# DSPCONN_4-7.net
KiCad netlist of a schematic drawn in Altium Designer
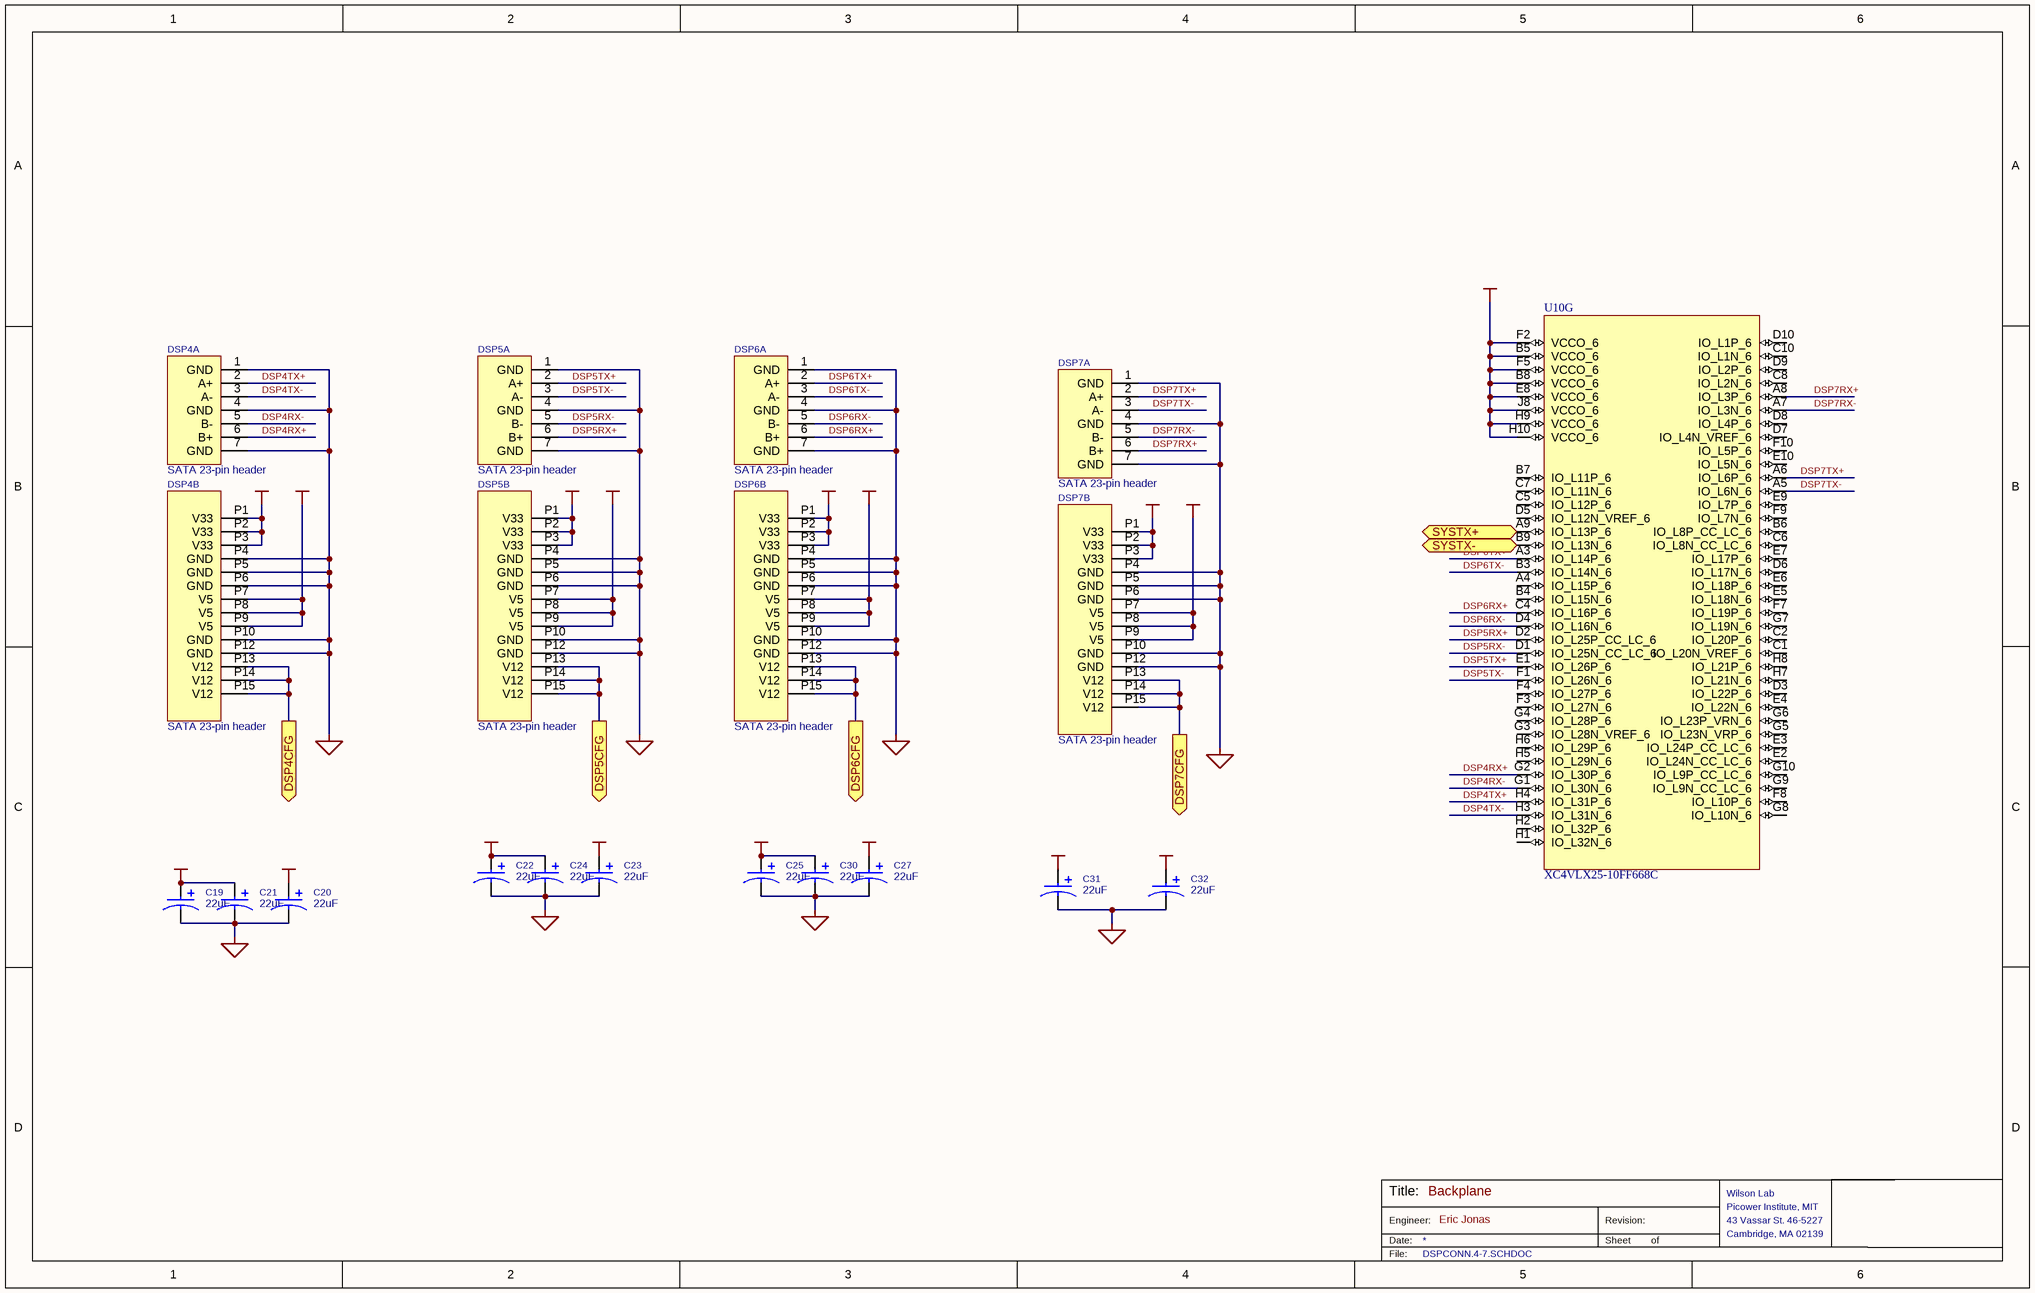
[diagram p0: DSPCONN.4-7.SCHDOC]

(export (version "E")
  (design (tool "Eeschema 10.0.6"))
  (components
    (comp (ref "C19")
      (value "22uF")
      (footprint "6032")
      (description "Standard Capacitor")
      (fields (field (name "Comment") "POLCAP2"))
      (libsource (lib "parts") (part "POLCAP2"))
    )
    (comp (ref "C20")
      (value "22uF")
      (footprint "6032")
      (description "Standard Capacitor")
      (fields (field (name "Comment") "POLCAP2"))
      (libsource (lib "parts") (part "POLCAP2"))
    )
    (comp (ref "C21")
      (value "22uF")
      (footprint "6032")
      (description "Standard Capacitor")
      (fields (field (name "Comment") "POLCAP2"))
      (libsource (lib "parts") (part "POLCAP2"))
    )
    (comp (ref "C22")
      (value "22uF")
      (footprint "6032")
      (description "Standard Capacitor")
      (fields (field (name "Comment") "POLCAP2"))
      (libsource (lib "parts") (part "POLCAP2"))
    )
    (comp (ref "C23")
      (value "22uF")
      (footprint "6032")
      (description "Standard Capacitor")
      (fields (field (name "Comment") "POLCAP2"))
      (libsource (lib "parts") (part "POLCAP2"))
    )
    (comp (ref "C24")
      (value "22uF")
      (footprint "6032")
      (description "Standard Capacitor")
      (fields (field (name "Comment") "POLCAP2"))
      (libsource (lib "parts") (part "POLCAP2"))
    )
    (comp (ref "C25")
      (value "22uF")
      (footprint "6032")
      (description "Standard Capacitor")
      (fields (field (name "Comment") "POLCAP2"))
      (libsource (lib "parts") (part "POLCAP2"))
    )
    (comp (ref "C27")
      (value "22uF")
      (footprint "6032")
      (description "Standard Capacitor")
      (fields (field (name "Comment") "POLCAP2"))
      (libsource (lib "parts") (part "POLCAP2"))
    )
    (comp (ref "C30")
      (value "22uF")
      (footprint "6032")
      (description "Standard Capacitor")
      (fields (field (name "Comment") "POLCAP2"))
      (libsource (lib "parts") (part "POLCAP2"))
    )
    (comp (ref "C31")
      (value "22uF")
      (footprint "6032")
      (description "Standard Capacitor")
      (fields (field (name "Comment") "POLCAP2"))
      (libsource (lib "parts") (part "POLCAP2"))
    )
    (comp (ref "C32")
      (value "22uF")
      (footprint "6032")
      (description "Standard Capacitor")
      (fields (field (name "Comment") "POLCAP2"))
      (libsource (lib "parts") (part "POLCAP2"))
    )
    (comp (ref "DSP4")
      (value "SATA 23-pin header")
      (footprint "MOLEX 87713-1001")
      (libsource (lib "parts") (part "SATA-23"))
    )
    (comp (ref "DSP5")
      (value "SATA 23-pin header")
      (footprint "MOLEX 87713-1001")
      (libsource (lib "parts") (part "SATA-23"))
    )
    (comp (ref "DSP6")
      (value "SATA 23-pin header")
      (footprint "MOLEX 87713-1001")
      (libsource (lib "parts") (part "SATA-23"))
    )
    (comp (ref "DSP7")
      (value "SATA 23-pin header")
      (footprint "MOLEX 87713-1001")
      (libsource (lib "parts") (part "SATA-23"))
    )
    (comp (ref "U10")
      (value "XC4VLX25-10FF668C")
      (footprint "Xilinx FF668")
      (description "Xilinx Virtex-4")
      (libsource (lib "parts") (part "XC4VLX25-10FF668C"))
    )
  )
  (nets
    (net (code "1") (name "+2.5VCC") (class "Default")
      (node (ref "U10") (pin "B5") (pinfunction "VCCO_6_B5") (pintype "bidirectional"))
      (node (ref "U10") (pin "B8") (pinfunction "VCCO_6_B8") (pintype "bidirectional"))
      (node (ref "U10") (pin "E8") (pinfunction "VCCO_6_E8") (pintype "bidirectional"))
      (node (ref "U10") (pin "F2") (pinfunction "VCCO_6_F2") (pintype "bidirectional"))
      (node (ref "U10") (pin "F5") (pinfunction "VCCO_6_F5") (pintype "bidirectional"))
      (node (ref "U10") (pin "H10") (pinfunction "VCCO_6_H10") (pintype "bidirectional"))
      (node (ref "U10") (pin "H9") (pinfunction "VCCO_6_H9") (pintype "bidirectional"))
      (node (ref "U10") (pin "J8") (pinfunction "VCCO_6_J8") (pintype "bidirectional"))
    )
    (net (code "2") (name "+5VCC") (class "Default")
      (node (ref "C20") (pin "1") (pintype "passive"))
      (node (ref "C23") (pin "1") (pintype "passive"))
      (node (ref "C27") (pin "1") (pintype "passive"))
      (node (ref "C32") (pin "1") (pintype "passive"))
      (node (ref "DSP4") (pin "P7") (pinfunction "V5_P7") (pintype "passive"))
      (node (ref "DSP4") (pin "P8") (pinfunction "V5_P8") (pintype "passive"))
      (node (ref "DSP4") (pin "P9") (pinfunction "V5_P9") (pintype "passive"))
      (node (ref "DSP5") (pin "P7") (pinfunction "V5_P7") (pintype "passive"))
      (node (ref "DSP5") (pin "P8") (pinfunction "V5_P8") (pintype "passive"))
      (node (ref "DSP5") (pin "P9") (pinfunction "V5_P9") (pintype "passive"))
      (node (ref "DSP6") (pin "P7") (pinfunction "V5_P7") (pintype "passive"))
      (node (ref "DSP6") (pin "P8") (pinfunction "V5_P8") (pintype "passive"))
      (node (ref "DSP6") (pin "P9") (pinfunction "V5_P9") (pintype "passive"))
      (node (ref "DSP7") (pin "P7") (pinfunction "V5_P7") (pintype "passive"))
      (node (ref "DSP7") (pin "P8") (pinfunction "V5_P8") (pintype "passive"))
      (node (ref "DSP7") (pin "P9") (pinfunction "V5_P9") (pintype "passive"))
    )
    (net (code "3") (name "/DSP4CFG") (class "Default")
      (node (ref "DSP4") (pin "P13") (pinfunction "V12_P13") (pintype "passive"))
      (node (ref "DSP4") (pin "P14") (pinfunction "V12_P14") (pintype "passive"))
      (node (ref "DSP4") (pin "P15") (pinfunction "V12_P15") (pintype "passive"))
    )
    (net (code "4") (name "/DSP4RX+") (class "Default")
      (node (ref "DSP4") (pin "6") (pinfunction "B+_6") (pintype "passive"))
      (node (ref "U10") (pin "G2") (pinfunction "IO_L30P_6_G2") (pintype "bidirectional"))
    )
    (net (code "5") (name "/DSP4RX-") (class "Default")
      (node (ref "DSP4") (pin "5") (pinfunction "B-_5") (pintype "passive"))
      (node (ref "U10") (pin "G1") (pinfunction "IO_L30N_6_G1") (pintype "bidirectional"))
    )
    (net (code "6") (name "/DSP4TX+") (class "Default")
      (node (ref "DSP4") (pin "2") (pinfunction "A+_2") (pintype "passive"))
      (node (ref "U10") (pin "H4") (pinfunction "IO_L31P_6_H4") (pintype "bidirectional"))
    )
    (net (code "7") (name "/DSP4TX-") (class "Default")
      (node (ref "DSP4") (pin "3") (pinfunction "A-_3") (pintype "passive"))
      (node (ref "U10") (pin "H3") (pinfunction "IO_L31N_6_H3") (pintype "bidirectional"))
    )
    (net (code "8") (name "/DSP5CFG") (class "Default")
      (node (ref "DSP5") (pin "P13") (pinfunction "V12_P13") (pintype "passive"))
      (node (ref "DSP5") (pin "P14") (pinfunction "V12_P14") (pintype "passive"))
      (node (ref "DSP5") (pin "P15") (pinfunction "V12_P15") (pintype "passive"))
    )
    (net (code "9") (name "/DSP5RX+") (class "Default")
      (node (ref "DSP5") (pin "6") (pinfunction "B+_6") (pintype "passive"))
      (node (ref "U10") (pin "D2") (pinfunction "IO_L25P_CC_LC_6_D2") (pintype "bidirectional"))
    )
    (net (code "10") (name "/DSP5RX-") (class "Default")
      (node (ref "DSP5") (pin "5") (pinfunction "B-_5") (pintype "passive"))
      (node (ref "U10") (pin "D1") (pinfunction "IO_L25N_CC_LC_6_D1") (pintype "bidirectional"))
    )
    (net (code "11") (name "/DSP5TX+") (class "Default")
      (node (ref "DSP5") (pin "2") (pinfunction "A+_2") (pintype "passive"))
      (node (ref "U10") (pin "E1") (pinfunction "IO_L26P_6_E1") (pintype "bidirectional"))
    )
    (net (code "12") (name "/DSP5TX-") (class "Default")
      (node (ref "DSP5") (pin "3") (pinfunction "A-_3") (pintype "passive"))
      (node (ref "U10") (pin "F1") (pinfunction "IO_L26N_6_F1") (pintype "bidirectional"))
    )
    (net (code "13") (name "/DSP6CFG") (class "Default")
      (node (ref "DSP6") (pin "P13") (pinfunction "V12_P13") (pintype "passive"))
      (node (ref "DSP6") (pin "P14") (pinfunction "V12_P14") (pintype "passive"))
      (node (ref "DSP6") (pin "P15") (pinfunction "V12_P15") (pintype "passive"))
    )
    (net (code "14") (name "/DSP6RX+") (class "Default")
      (node (ref "DSP6") (pin "6") (pinfunction "B+_6") (pintype "passive"))
      (node (ref "U10") (pin "C4") (pinfunction "IO_L16P_6_C4") (pintype "bidirectional"))
    )
    (net (code "15") (name "/DSP6RX-") (class "Default")
      (node (ref "DSP6") (pin "5") (pinfunction "B-_5") (pintype "passive"))
      (node (ref "U10") (pin "D4") (pinfunction "IO_L16N_6_D4") (pintype "bidirectional"))
    )
    (net (code "16") (name "/DSP6TX+") (class "Default")
      (node (ref "DSP6") (pin "2") (pinfunction "A+_2") (pintype "passive"))
      (node (ref "U10") (pin "A3") (pinfunction "IO_L14P_6_A3") (pintype "bidirectional"))
    )
    (net (code "17") (name "/DSP6TX-") (class "Default")
      (node (ref "DSP6") (pin "3") (pinfunction "A-_3") (pintype "passive"))
      (node (ref "U10") (pin "B3") (pinfunction "IO_L14N_6_B3") (pintype "bidirectional"))
    )
    (net (code "18") (name "/DSP7CFG") (class "Default")
      (node (ref "DSP7") (pin "P13") (pinfunction "V12_P13") (pintype "passive"))
      (node (ref "DSP7") (pin "P14") (pinfunction "V12_P14") (pintype "passive"))
      (node (ref "DSP7") (pin "P15") (pinfunction "V12_P15") (pintype "passive"))
    )
    (net (code "19") (name "/DSP7RX+") (class "Default")
      (node (ref "DSP7") (pin "6") (pinfunction "B+_6") (pintype "passive"))
      (node (ref "U10") (pin "A8") (pinfunction "IO_L3P_6_A8") (pintype "bidirectional"))
    )
    (net (code "20") (name "/DSP7RX-") (class "Default")
      (node (ref "DSP7") (pin "5") (pinfunction "B-_5") (pintype "passive"))
      (node (ref "U10") (pin "A7") (pinfunction "IO_L3N_6_A7") (pintype "bidirectional"))
    )
    (net (code "21") (name "/DSP7TX+") (class "Default")
      (node (ref "DSP7") (pin "2") (pinfunction "A+_2") (pintype "passive"))
      (node (ref "U10") (pin "A6") (pinfunction "IO_L6P_6_A6") (pintype "bidirectional"))
    )
    (net (code "22") (name "/DSP7TX-") (class "Default")
      (node (ref "DSP7") (pin "3") (pinfunction "A-_3") (pintype "passive"))
      (node (ref "U10") (pin "A5") (pinfunction "IO_L6N_6_A5") (pintype "bidirectional"))
    )
    (net (code "23") (name "/SYSTX+") (class "Default")
      (node (ref "U10") (pin "A9") (pinfunction "IO_L13P_6_A9") (pintype "bidirectional"))
    )
    (net (code "24") (name "/SYSTX-") (class "Default")
      (node (ref "U10") (pin "B9") (pinfunction "IO_L13N_6_B9") (pintype "bidirectional"))
    )
    (net (code "25") (name "GND") (class "Default")
      (node (ref "C19") (pin "2") (pintype "passive"))
      (node (ref "C20") (pin "2") (pintype "passive"))
      (node (ref "C21") (pin "2") (pintype "passive"))
      (node (ref "C22") (pin "2") (pintype "passive"))
      (node (ref "C23") (pin "2") (pintype "passive"))
      (node (ref "C24") (pin "2") (pintype "passive"))
      (node (ref "C25") (pin "2") (pintype "passive"))
      (node (ref "C27") (pin "2") (pintype "passive"))
      (node (ref "C30") (pin "2") (pintype "passive"))
      (node (ref "C31") (pin "2") (pintype "passive"))
      (node (ref "C32") (pin "2") (pintype "passive"))
      (node (ref "DSP4") (pin "1") (pinfunction "GND_1") (pintype "passive"))
      (node (ref "DSP4") (pin "4") (pinfunction "GND_4") (pintype "passive"))
      (node (ref "DSP4") (pin "7") (pinfunction "GND_7") (pintype "passive"))
      (node (ref "DSP4") (pin "P10") (pinfunction "GND_P10") (pintype "passive"))
      (node (ref "DSP4") (pin "P12") (pinfunction "GND_P12") (pintype "passive"))
      (node (ref "DSP4") (pin "P4") (pinfunction "GND_P4") (pintype "passive"))
      (node (ref "DSP4") (pin "P5") (pinfunction "GND_P5") (pintype "passive"))
      (node (ref "DSP4") (pin "P6") (pinfunction "GND_P6") (pintype "passive"))
      (node (ref "DSP5") (pin "1") (pinfunction "GND_1") (pintype "passive"))
      (node (ref "DSP5") (pin "4") (pinfunction "GND_4") (pintype "passive"))
      (node (ref "DSP5") (pin "7") (pinfunction "GND_7") (pintype "passive"))
      (node (ref "DSP5") (pin "P10") (pinfunction "GND_P10") (pintype "passive"))
      (node (ref "DSP5") (pin "P12") (pinfunction "GND_P12") (pintype "passive"))
      (node (ref "DSP5") (pin "P4") (pinfunction "GND_P4") (pintype "passive"))
      (node (ref "DSP5") (pin "P5") (pinfunction "GND_P5") (pintype "passive"))
      (node (ref "DSP5") (pin "P6") (pinfunction "GND_P6") (pintype "passive"))
      (node (ref "DSP6") (pin "1") (pinfunction "GND_1") (pintype "passive"))
      (node (ref "DSP6") (pin "4") (pinfunction "GND_4") (pintype "passive"))
      (node (ref "DSP6") (pin "7") (pinfunction "GND_7") (pintype "passive"))
      (node (ref "DSP6") (pin "P10") (pinfunction "GND_P10") (pintype "passive"))
      (node (ref "DSP6") (pin "P12") (pinfunction "GND_P12") (pintype "passive"))
      (node (ref "DSP6") (pin "P4") (pinfunction "GND_P4") (pintype "passive"))
      (node (ref "DSP6") (pin "P5") (pinfunction "GND_P5") (pintype "passive"))
      (node (ref "DSP6") (pin "P6") (pinfunction "GND_P6") (pintype "passive"))
      (node (ref "DSP7") (pin "1") (pinfunction "GND_1") (pintype "passive"))
      (node (ref "DSP7") (pin "4") (pinfunction "GND_4") (pintype "passive"))
      (node (ref "DSP7") (pin "7") (pinfunction "GND_7") (pintype "passive"))
      (node (ref "DSP7") (pin "P10") (pinfunction "GND_P10") (pintype "passive"))
      (node (ref "DSP7") (pin "P12") (pinfunction "GND_P12") (pintype "passive"))
      (node (ref "DSP7") (pin "P4") (pinfunction "GND_P4") (pintype "passive"))
      (node (ref "DSP7") (pin "P5") (pinfunction "GND_P5") (pintype "passive"))
      (node (ref "DSP7") (pin "P6") (pinfunction "GND_P6") (pintype "passive"))
    )
    (net (code "26") (name "VCC") (class "Default")
      (node (ref "C19") (pin "1") (pintype "passive"))
      (node (ref "C21") (pin "1") (pintype "passive"))
      (node (ref "C22") (pin "1") (pintype "passive"))
      (node (ref "C24") (pin "1") (pintype "passive"))
      (node (ref "C25") (pin "1") (pintype "passive"))
      (node (ref "C30") (pin "1") (pintype "passive"))
      (node (ref "C31") (pin "1") (pintype "passive"))
      (node (ref "DSP4") (pin "P1") (pinfunction "V33_P1") (pintype "passive"))
      (node (ref "DSP4") (pin "P2") (pinfunction "V33_P2") (pintype "passive"))
      (node (ref "DSP4") (pin "P3") (pinfunction "V33_P3") (pintype "passive"))
      (node (ref "DSP5") (pin "P1") (pinfunction "V33_P1") (pintype "passive"))
      (node (ref "DSP5") (pin "P2") (pinfunction "V33_P2") (pintype "passive"))
      (node (ref "DSP5") (pin "P3") (pinfunction "V33_P3") (pintype "passive"))
      (node (ref "DSP6") (pin "P1") (pinfunction "V33_P1") (pintype "passive"))
      (node (ref "DSP6") (pin "P2") (pinfunction "V33_P2") (pintype "passive"))
      (node (ref "DSP6") (pin "P3") (pinfunction "V33_P3") (pintype "passive"))
      (node (ref "DSP7") (pin "P1") (pinfunction "V33_P1") (pintype "passive"))
      (node (ref "DSP7") (pin "P2") (pinfunction "V33_P2") (pintype "passive"))
      (node (ref "DSP7") (pin "P3") (pinfunction "V33_P3") (pintype "passive"))
    )
    (net (code "27") (name "unconnected-(U10G-IO_L1N_6-PadC10)") (class "Default")
      (node (ref "U10") (pin "C10") (pinfunction "IO_L1N_6_C10") (pintype "bidirectional"))
    )
    (net (code "28") (name "unconnected-(U10G-IO_L1P_6-PadD10)") (class "Default")
      (node (ref "U10") (pin "D10") (pinfunction "IO_L1P_6_D10") (pintype "bidirectional"))
    )
    (net (code "29") (name "unconnected-(U10G-IO_L2N_6-PadC8)") (class "Default")
      (node (ref "U10") (pin "C8") (pinfunction "IO_L2N_6_C8") (pintype "bidirectional"))
    )
    (net (code "30") (name "unconnected-(U10G-IO_L2P_6-PadD9)") (class "Default")
      (node (ref "U10") (pin "D9") (pinfunction "IO_L2P_6_D9") (pintype "bidirectional"))
    )
    (net (code "31") (name "unconnected-(U10G-IO_L4N_VREF_6-PadD7)") (class "Default")
      (node (ref "U10") (pin "D7") (pinfunction "IO_L4N_VREF_6_D7") (pintype "bidirectional"))
    )
    (net (code "32") (name "unconnected-(U10G-IO_L4P_6-PadD8)") (class "Default")
      (node (ref "U10") (pin "D8") (pinfunction "IO_L4P_6_D8") (pintype "bidirectional"))
    )
    (net (code "33") (name "unconnected-(U10G-IO_L5N_6-PadE10)") (class "Default")
      (node (ref "U10") (pin "E10") (pinfunction "IO_L5N_6_E10") (pintype "bidirectional"))
    )
    (net (code "34") (name "unconnected-(U10G-IO_L5P_6-PadF10)") (class "Default")
      (node (ref "U10") (pin "F10") (pinfunction "IO_L5P_6_F10") (pintype "bidirectional"))
    )
    (net (code "35") (name "unconnected-(U10G-IO_L7N_6-PadF9)") (class "Default")
      (node (ref "U10") (pin "F9") (pinfunction "IO_L7N_6_F9") (pintype "bidirectional"))
    )
    (net (code "36") (name "unconnected-(U10G-IO_L7P_6-PadE9)") (class "Default")
      (node (ref "U10") (pin "E9") (pinfunction "IO_L7P_6_E9") (pintype "bidirectional"))
    )
    (net (code "37") (name "unconnected-(U10G-IO_L8N_CC_LC_6-PadC6)") (class "Default")
      (node (ref "U10") (pin "C6") (pinfunction "IO_L8N_CC_LC_6_C6") (pintype "bidirectional"))
    )
    (net (code "38") (name "unconnected-(U10G-IO_L8P_CC_LC_6-PadB6)") (class "Default")
      (node (ref "U10") (pin "B6") (pinfunction "IO_L8P_CC_LC_6_B6") (pintype "bidirectional"))
    )
    (net (code "39") (name "unconnected-(U10G-IO_L9N_CC_LC_6-PadG9)") (class "Default")
      (node (ref "U10") (pin "G9") (pinfunction "IO_L9N_CC_LC_6_G9") (pintype "bidirectional"))
    )
    (net (code "40") (name "unconnected-(U10G-IO_L9P_CC_LC_6-PadG10)") (class "Default")
      (node (ref "U10") (pin "G10") (pinfunction "IO_L9P_CC_LC_6_G10") (pintype "bidirectional"))
    )
    (net (code "41") (name "unconnected-(U10G-IO_L10N_6-PadG8)") (class "Default")
      (node (ref "U10") (pin "G8") (pinfunction "IO_L10N_6_G8") (pintype "bidirectional"))
    )
    (net (code "42") (name "unconnected-(U10G-IO_L10P_6-PadF8)") (class "Default")
      (node (ref "U10") (pin "F8") (pinfunction "IO_L10P_6_F8") (pintype "bidirectional"))
    )
    (net (code "43") (name "unconnected-(U10G-IO_L11N_6-PadC7)") (class "Default")
      (node (ref "U10") (pin "C7") (pinfunction "IO_L11N_6_C7") (pintype "bidirectional"))
    )
    (net (code "44") (name "unconnected-(U10G-IO_L11P_6-PadB7)") (class "Default")
      (node (ref "U10") (pin "B7") (pinfunction "IO_L11P_6_B7") (pintype "bidirectional"))
    )
    (net (code "45") (name "unconnected-(U10G-IO_L12N_VREF_6-PadD5)") (class "Default")
      (node (ref "U10") (pin "D5") (pinfunction "IO_L12N_VREF_6_D5") (pintype "bidirectional"))
    )
    (net (code "46") (name "unconnected-(U10G-IO_L12P_6-PadC5)") (class "Default")
      (node (ref "U10") (pin "C5") (pinfunction "IO_L12P_6_C5") (pintype "bidirectional"))
    )
    (net (code "47") (name "unconnected-(U10G-IO_L15N_6-PadB4)") (class "Default")
      (node (ref "U10") (pin "B4") (pinfunction "IO_L15N_6_B4") (pintype "bidirectional"))
    )
    (net (code "48") (name "unconnected-(U10G-IO_L15P_6-PadA4)") (class "Default")
      (node (ref "U10") (pin "A4") (pinfunction "IO_L15P_6_A4") (pintype "bidirectional"))
    )
    (net (code "49") (name "unconnected-(U10G-IO_L17N_6-PadD6)") (class "Default")
      (node (ref "U10") (pin "D6") (pinfunction "IO_L17N_6_D6") (pintype "bidirectional"))
    )
    (net (code "50") (name "unconnected-(U10G-IO_L17P_6-PadE7)") (class "Default")
      (node (ref "U10") (pin "E7") (pinfunction "IO_L17P_6_E7") (pintype "bidirectional"))
    )
    (net (code "51") (name "unconnected-(U10G-IO_L18N_6-PadE5)") (class "Default")
      (node (ref "U10") (pin "E5") (pinfunction "IO_L18N_6_E5") (pintype "bidirectional"))
    )
    (net (code "52") (name "unconnected-(U10G-IO_L18P_6-PadE6)") (class "Default")
      (node (ref "U10") (pin "E6") (pinfunction "IO_L18P_6_E6") (pintype "bidirectional"))
    )
    (net (code "53") (name "unconnected-(U10G-IO_L19N_6-PadG7)") (class "Default")
      (node (ref "U10") (pin "G7") (pinfunction "IO_L19N_6_G7") (pintype "bidirectional"))
    )
    (net (code "54") (name "unconnected-(U10G-IO_L19P_6-PadF7)") (class "Default")
      (node (ref "U10") (pin "F7") (pinfunction "IO_L19P_6_F7") (pintype "bidirectional"))
    )
    (net (code "55") (name "unconnected-(U10G-IO_L20N_VREF_6-PadC1)") (class "Default")
      (node (ref "U10") (pin "C1") (pinfunction "IO_L20N_VREF_6_C1") (pintype "bidirectional"))
    )
    (net (code "56") (name "unconnected-(U10G-IO_L20P_6-PadC2)") (class "Default")
      (node (ref "U10") (pin "C2") (pinfunction "IO_L20P_6_C2") (pintype "bidirectional"))
    )
    (net (code "57") (name "unconnected-(U10G-IO_L21N_6-PadH7)") (class "Default")
      (node (ref "U10") (pin "H7") (pinfunction "IO_L21N_6_H7") (pintype "bidirectional"))
    )
    (net (code "58") (name "unconnected-(U10G-IO_L21P_6-PadH8)") (class "Default")
      (node (ref "U10") (pin "H8") (pinfunction "IO_L21P_6_H8") (pintype "bidirectional"))
    )
    (net (code "59") (name "unconnected-(U10G-IO_L22N_6-PadE4)") (class "Default")
      (node (ref "U10") (pin "E4") (pinfunction "IO_L22N_6_E4") (pintype "bidirectional"))
    )
    (net (code "60") (name "unconnected-(U10G-IO_L22P_6-PadD3)") (class "Default")
      (node (ref "U10") (pin "D3") (pinfunction "IO_L22P_6_D3") (pintype "bidirectional"))
    )
    (net (code "61") (name "unconnected-(U10G-IO_L23N_VRP_6-PadG5)") (class "Default")
      (node (ref "U10") (pin "G5") (pinfunction "IO_L23N_VRP_6_G5") (pintype "bidirectional"))
    )
    (net (code "62") (name "unconnected-(U10G-IO_L23P_VRN_6-PadG6)") (class "Default")
      (node (ref "U10") (pin "G6") (pinfunction "IO_L23P_VRN_6_G6") (pintype "bidirectional"))
    )
    (net (code "63") (name "unconnected-(U10G-IO_L24N_CC_LC_6-PadE2)") (class "Default")
      (node (ref "U10") (pin "E2") (pinfunction "IO_L24N_CC_LC_6_E2") (pintype "bidirectional"))
    )
    (net (code "64") (name "unconnected-(U10G-IO_L24P_CC_LC_6-PadE3)") (class "Default")
      (node (ref "U10") (pin "E3") (pinfunction "IO_L24P_CC_LC_6_E3") (pintype "bidirectional"))
    )
    (net (code "65") (name "unconnected-(U10G-IO_L27N_6-PadF3)") (class "Default")
      (node (ref "U10") (pin "F3") (pinfunction "IO_L27N_6_F3") (pintype "bidirectional"))
    )
    (net (code "66") (name "unconnected-(U10G-IO_L27P_6-PadF4)") (class "Default")
      (node (ref "U10") (pin "F4") (pinfunction "IO_L27P_6_F4") (pintype "bidirectional"))
    )
    (net (code "67") (name "unconnected-(U10G-IO_L28N_VREF_6-PadG3)") (class "Default")
      (node (ref "U10") (pin "G3") (pinfunction "IO_L28N_VREF_6_G3") (pintype "bidirectional"))
    )
    (net (code "68") (name "unconnected-(U10G-IO_L28P_6-PadG4)") (class "Default")
      (node (ref "U10") (pin "G4") (pinfunction "IO_L28P_6_G4") (pintype "bidirectional"))
    )
    (net (code "69") (name "unconnected-(U10G-IO_L29N_6-PadH5)") (class "Default")
      (node (ref "U10") (pin "H5") (pinfunction "IO_L29N_6_H5") (pintype "bidirectional"))
    )
    (net (code "70") (name "unconnected-(U10G-IO_L29P_6-PadH6)") (class "Default")
      (node (ref "U10") (pin "H6") (pinfunction "IO_L29P_6_H6") (pintype "bidirectional"))
    )
    (net (code "71") (name "unconnected-(U10G-IO_L32N_6-PadH1)") (class "Default")
      (node (ref "U10") (pin "H1") (pinfunction "IO_L32N_6_H1") (pintype "bidirectional"))
    )
    (net (code "72") (name "unconnected-(U10G-IO_L32P_6-PadH2)") (class "Default")
      (node (ref "U10") (pin "H2") (pinfunction "IO_L32P_6_H2") (pintype "bidirectional"))
    )
  )
)
